# 1-Schematic_testflight2_pcb.net
KiCad netlist of a schematic drawn in EasyEDA
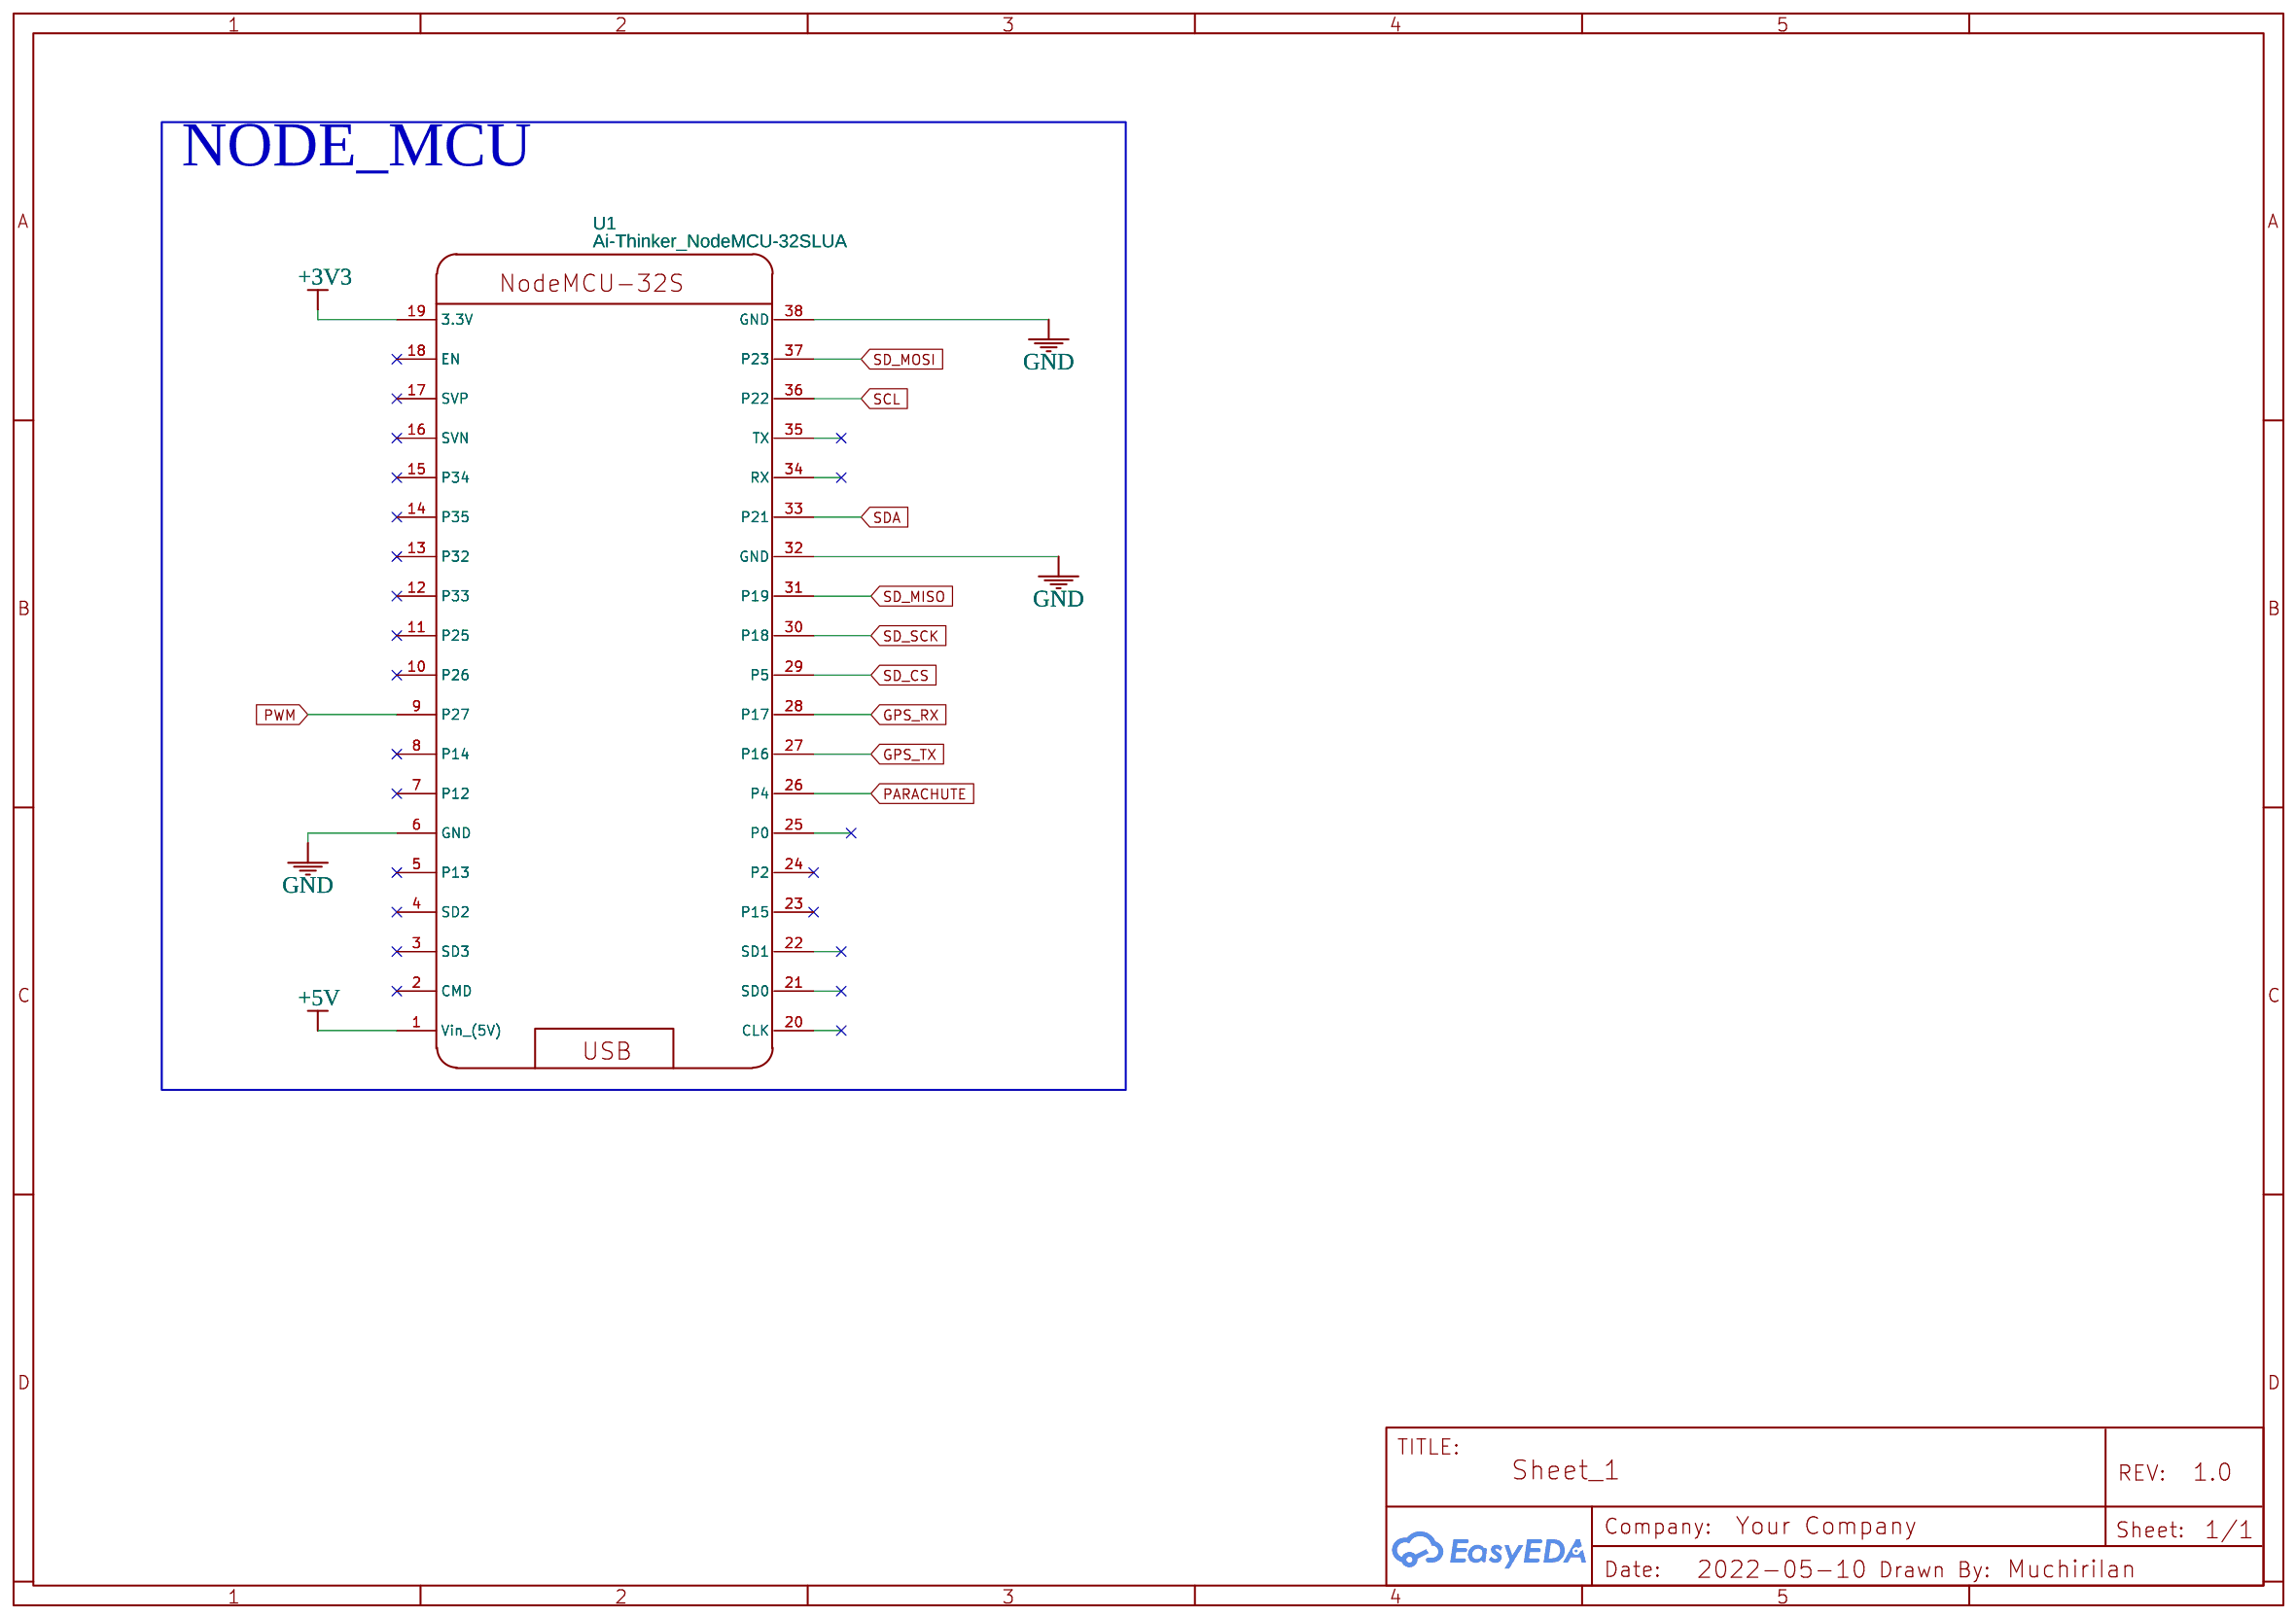
[diagram p0: Sheet_1]
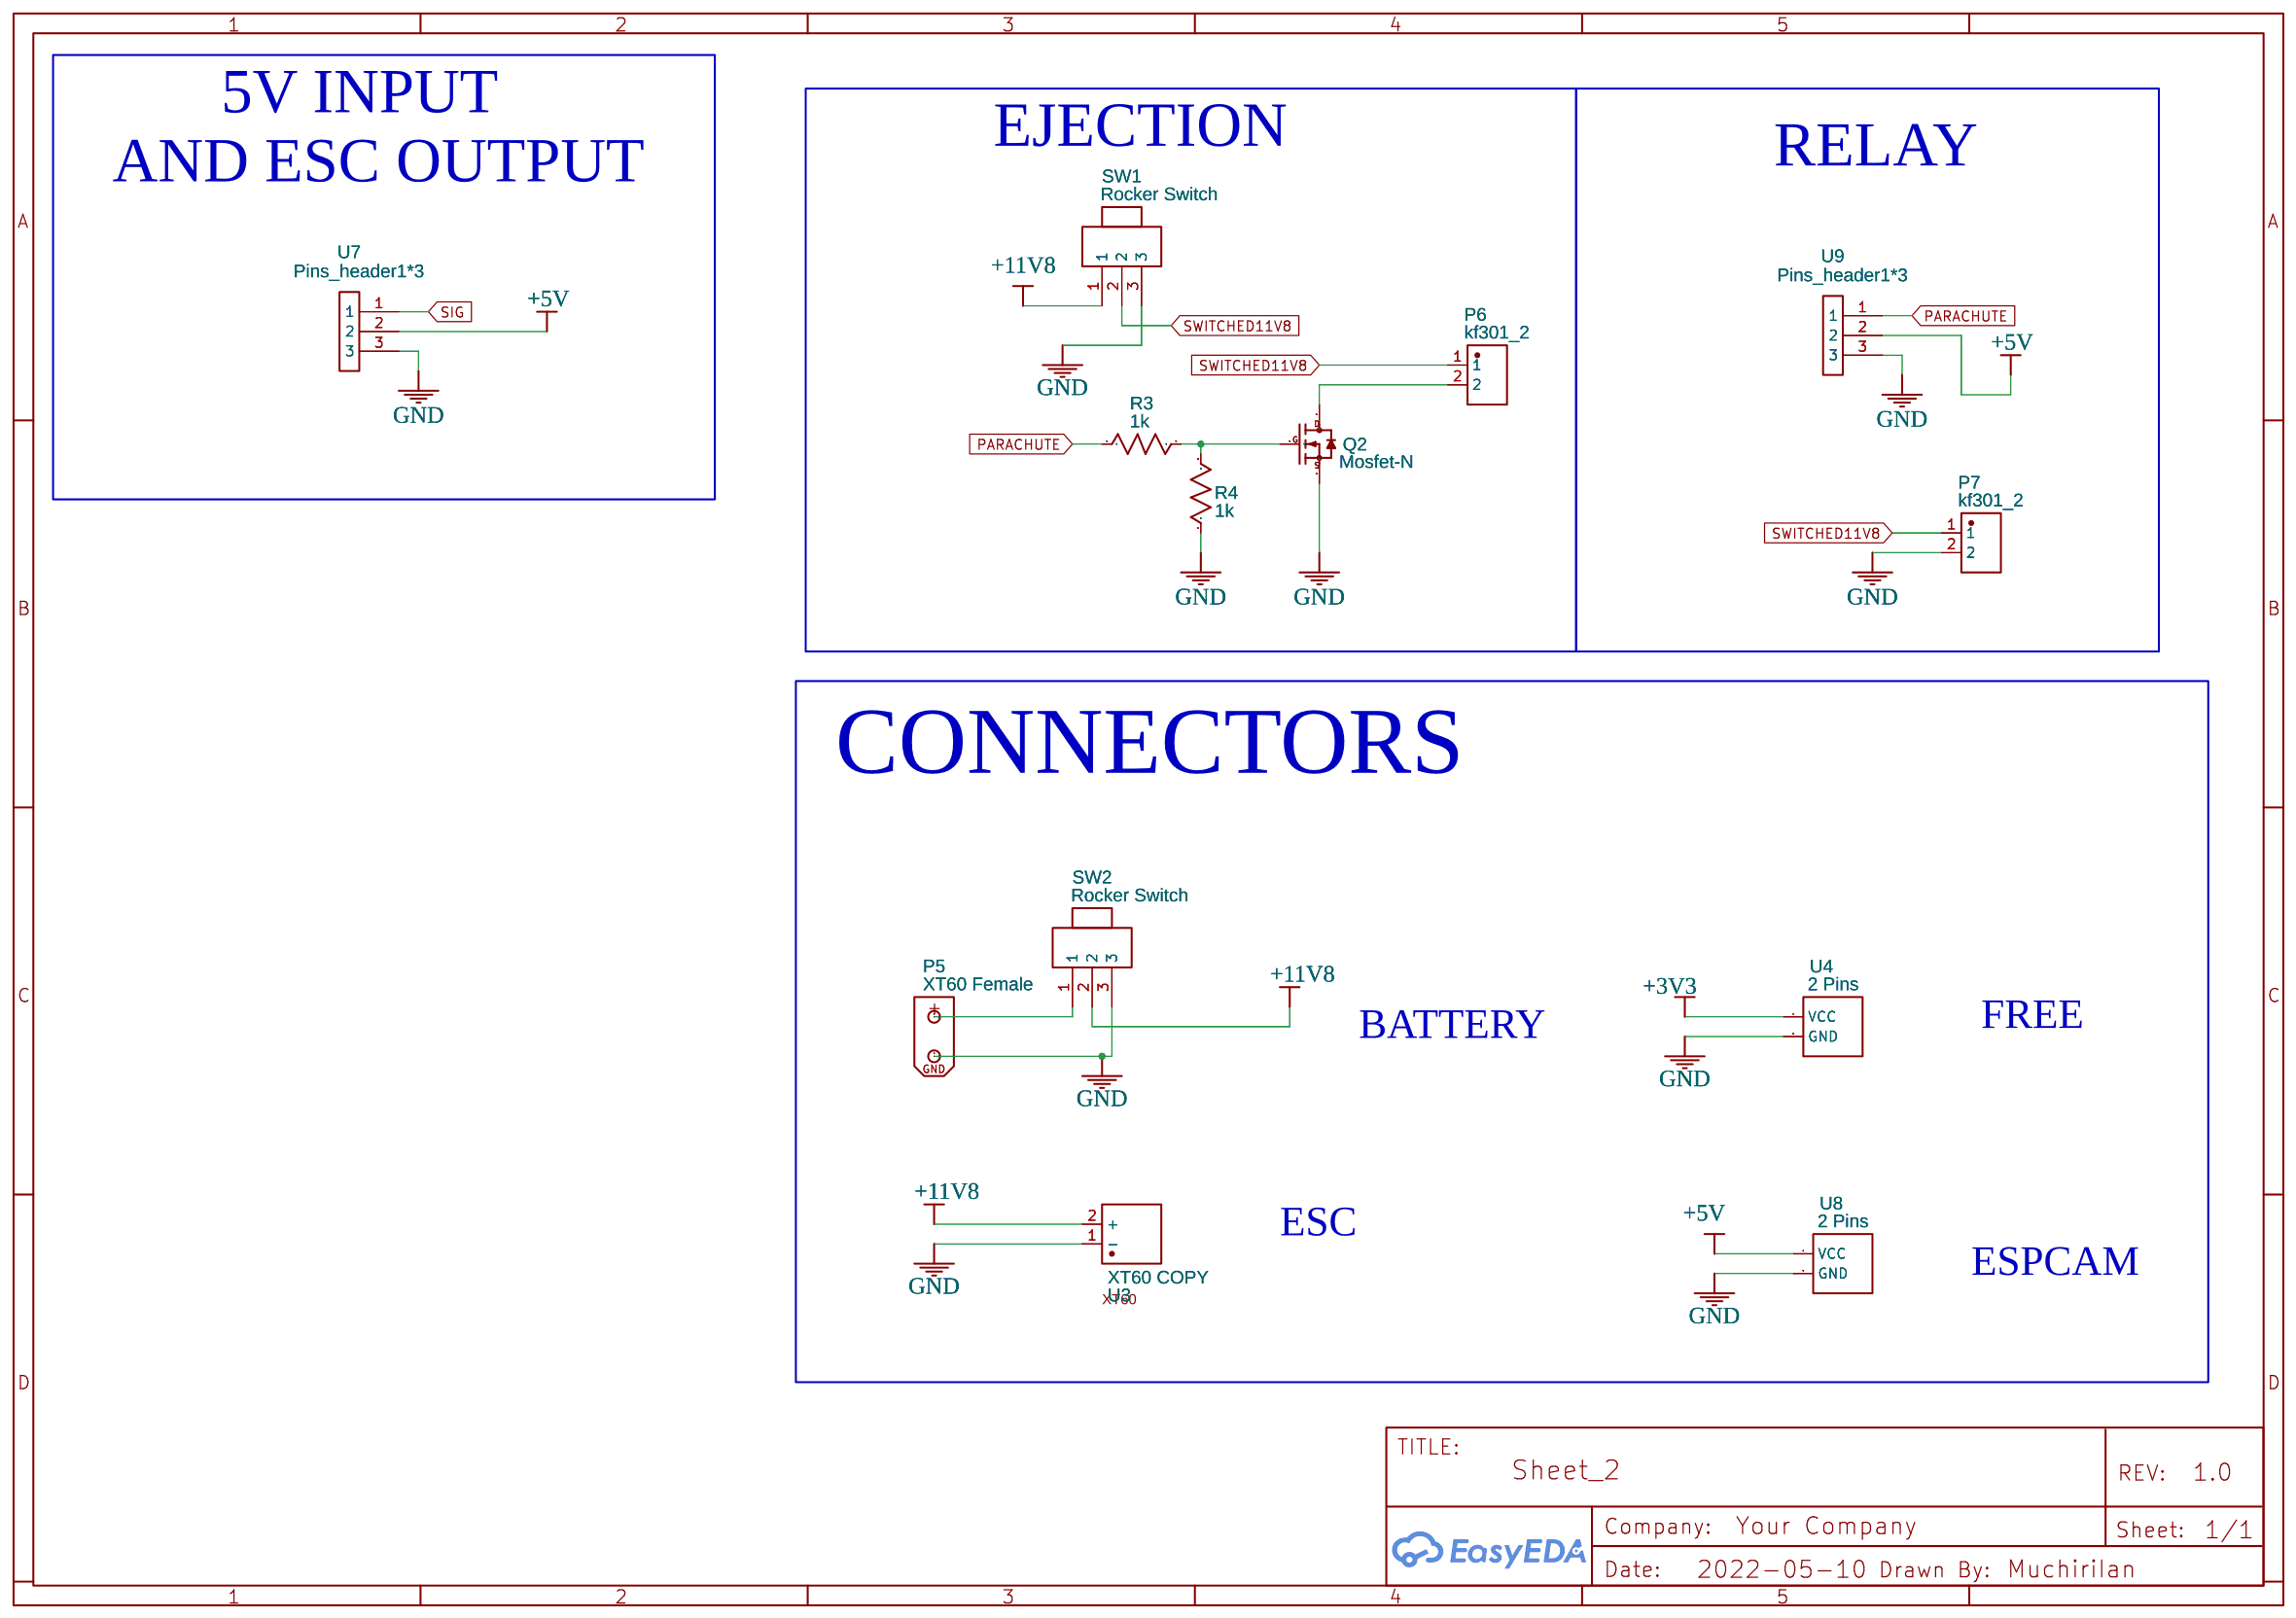
[diagram p1: Sheet_2]
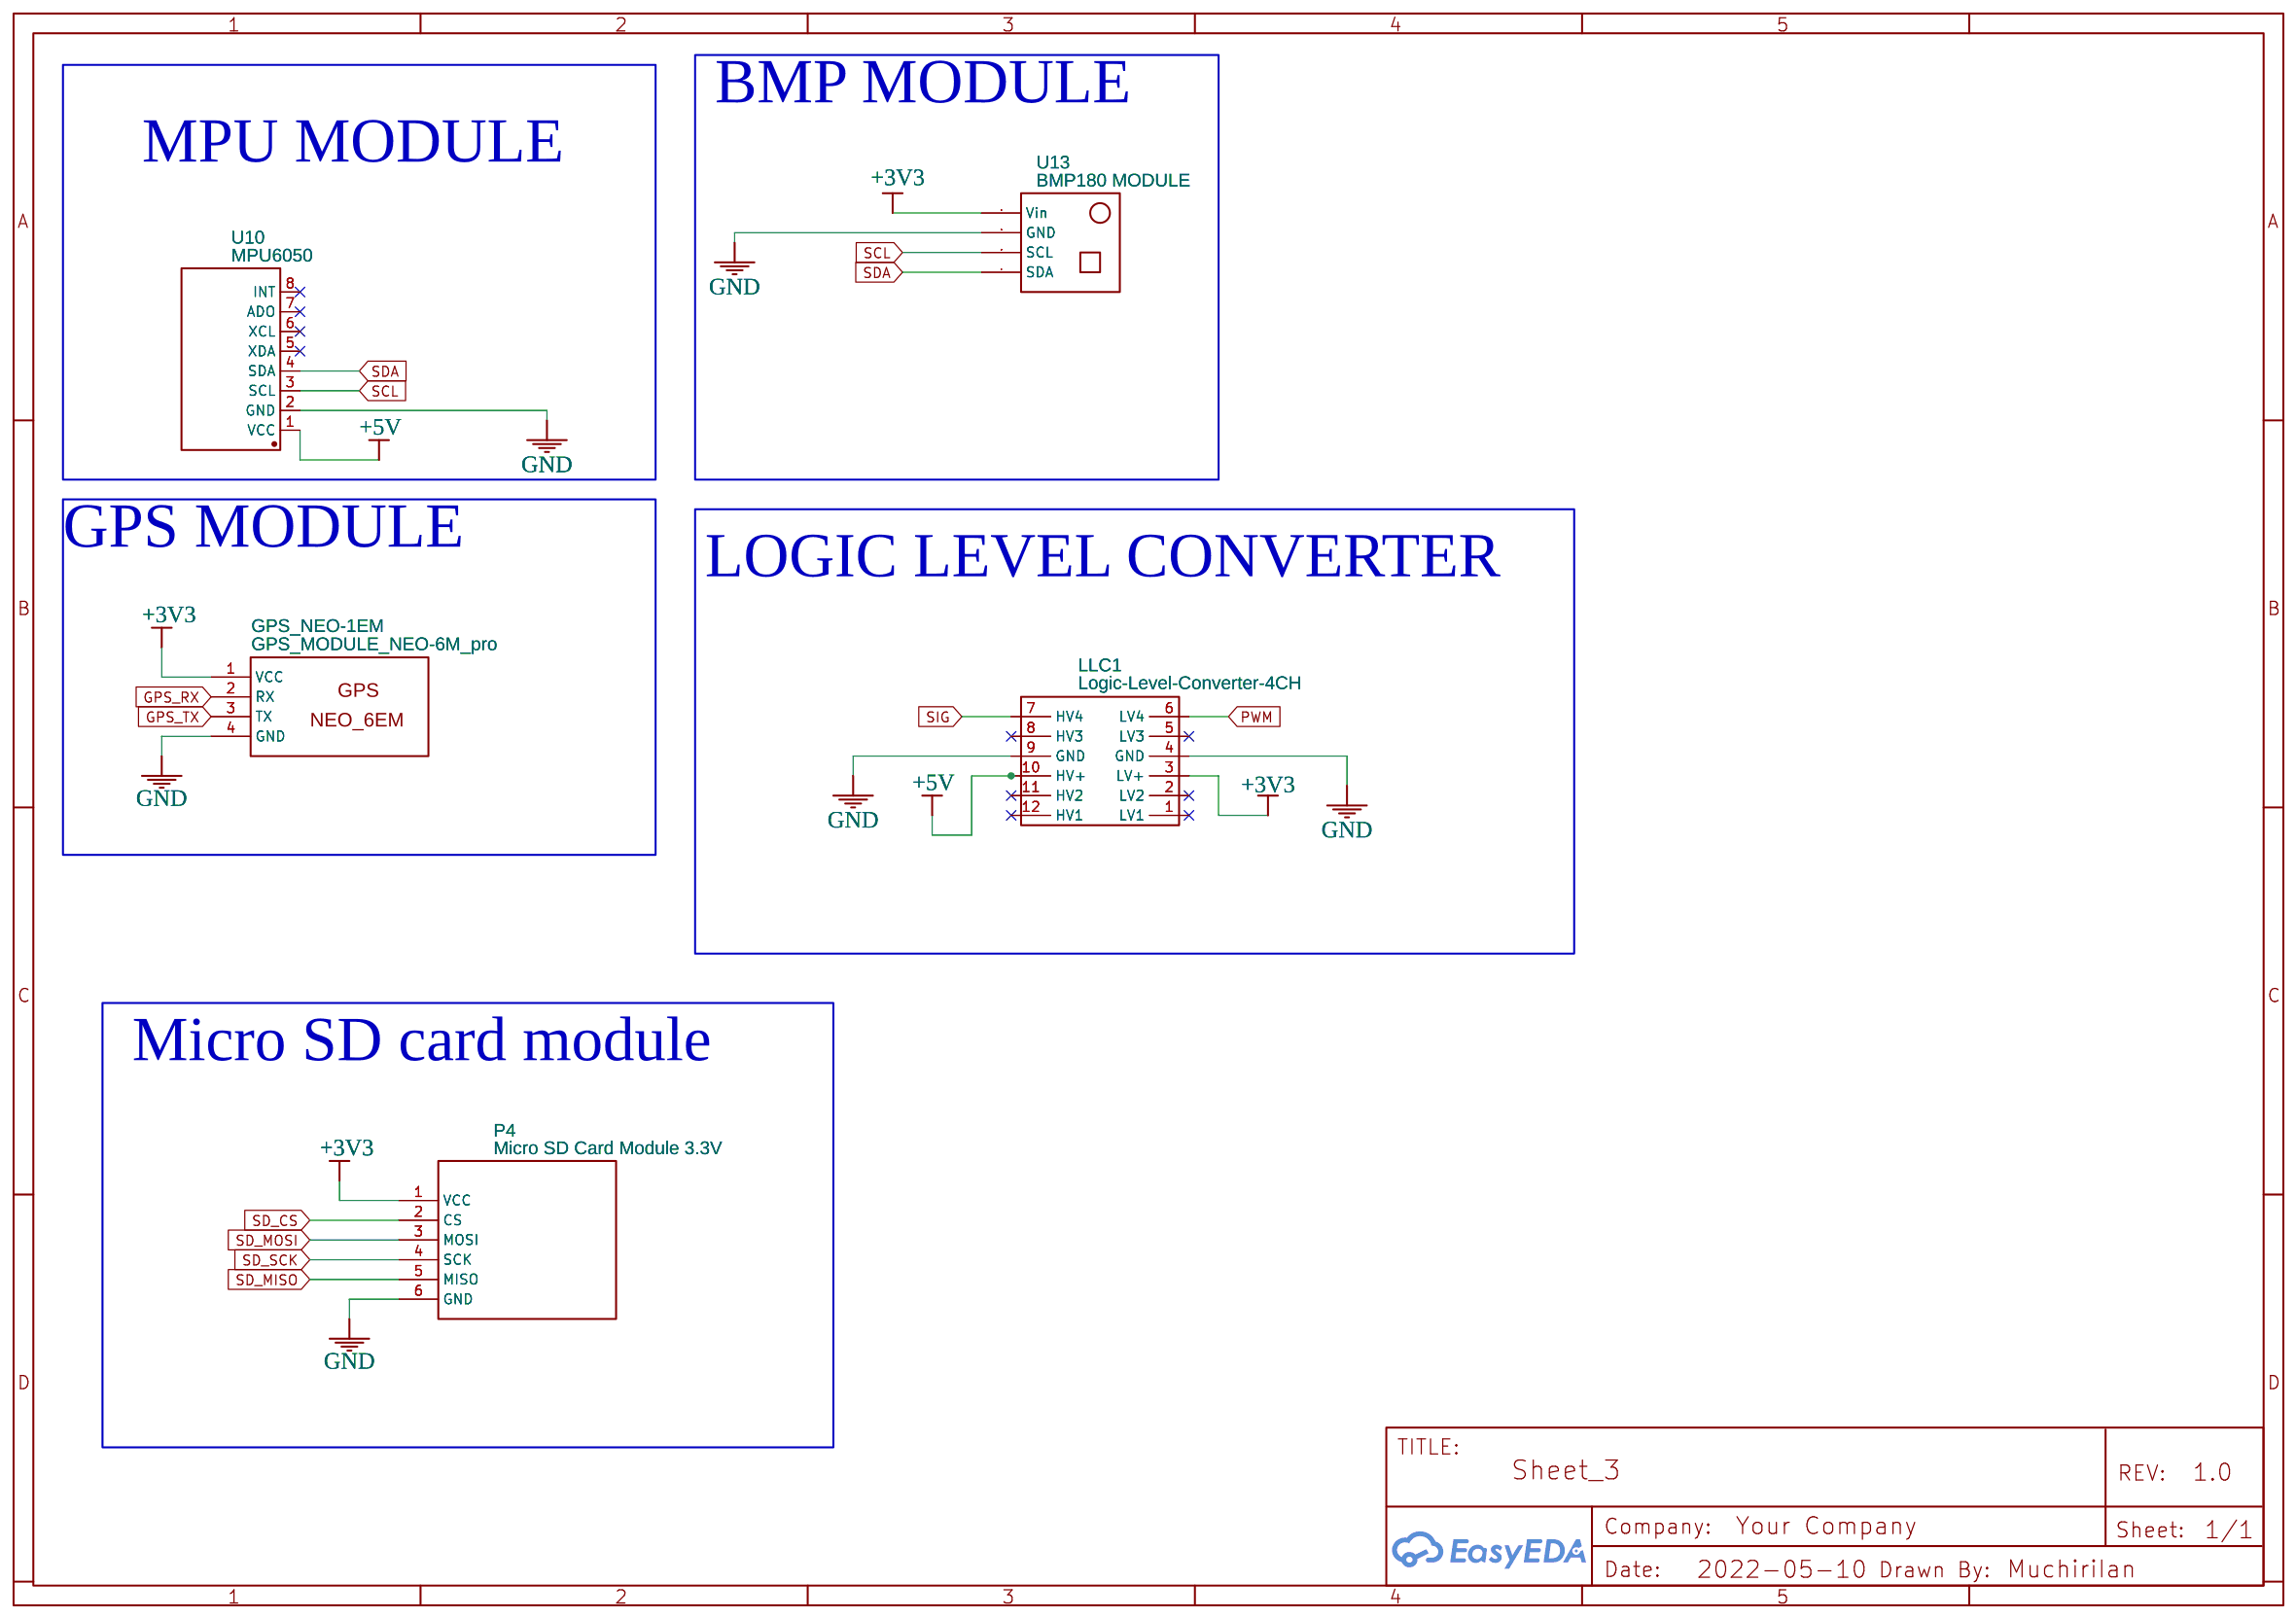
[diagram p2: Sheet_3]

(export (version "E")
  (design (tool "Eeschema 10.0.6"))
  (components
    (comp (ref "U1")
      (value "Ai-Thinker_NodeMCU-32SLUA")
      (fields
        (field (name "BOM_Manufacturer Part") "NodeMCU-32SLua")
        (field (name "BOM_Supplier Part") "C111436")
      )
      (libsource (lib "") (part "Ai-Thinker_NodeMCU-32SLUA"))
    )
    (comp (ref "P5")
      (value "XT60 Female")
      (fields (field (name "BOM_Manufacturer Part") "XT60-F"))
      (libsource (lib "") (part "XT60 Female"))
    )
    (comp (ref "P6")
      (value "kf301_2")
      (fields (field (name "BOM_Supplier Part") "C33435"))
      (libsource (lib "") (part "kf301_2"))
    )
    (comp (ref "P7")
      (value "kf301_2")
      (fields (field (name "BOM_Supplier Part") "C33435"))
      (libsource (lib "") (part "kf301_2"))
    )
    (comp (ref "Q2") (value "Mosfet-N") (libsource (lib "") (part "Mosfet-N")))
    (comp (ref "R3") (value "1k") (libsource (lib "") (part "R_AXIAL-0.6_US")))
    (comp (ref "R4") (value "1k") (libsource (lib "") (part "R_AXIAL-0.6_US_1")))
    (comp (ref "SW1") (value "Rocker Switch") (libsource (lib "") (part "Rocker Switch")))
    (comp (ref "SW2") (value "Rocker Switch") (libsource (lib "") (part "Rocker Switch")))
    (comp (ref "U3") (value "XT60 COPY") (libsource (lib "") (part "XT60 COPY")))
    (comp (ref "U4") (value "2 Pins") (libsource (lib "") (part "2 Pins")))
    (comp (ref "U7") (value "Pins_header1*3") (libsource (lib "") (part "Pins_header1*3")))
    (comp (ref "U8") (value "2 Pins") (libsource (lib "") (part "2 Pins")))
    (comp (ref "U9") (value "Pins_header1*3") (libsource (lib "") (part "Pins_header1*3")))
    (comp (ref "GPS_NEO-1EM")
      (value "GPS_MODULE_NEO-6M_pro")
      (libsource (lib "") (part "GPS_MODULE_NEO-6M_pro"))
    )
    (comp (ref "LLC1")
      (value "Logic-Level-Converter-4CH")
      (fields (field (name "BOM_Supplier Part") "50807"))
      (libsource (lib "") (part "Logic-Level-Converter-4CH"))
    )
    (comp (ref "P4")
      (value "Micro SD Card Module 3.3V")
      (libsource (lib "") (part "Micro SD Card Module 3.3V"))
    )
    (comp (ref "U10")
      (value "MPU6050")
      (fields (field (name "BOM_Supplier Part") "GY521"))
      (libsource (lib "") (part "MPU6050"))
    )
    (comp (ref "U13")
      (value "BMP180 MODULE")
      (fields (field (name "BOM_Manufacturer Part") "BMP180 (HW-596)"))
      (libsource (lib "") (part "BMP180 MODULE"))
    )
  )
  (nets
    (net (code "1") (name "+3V3") (class "Default")
      (node (ref "GPS_NEO-1EM") (pin "1") (pinfunction "VCC_1") (pintype "passive"))
      (node (ref "LLC1") (pin "3") (pinfunction "LV+_3") (pintype "unspecified"))
      (node (ref "P4") (pin "1") (pinfunction "VCC_1") (pintype "unspecified"))
      (node (ref "U1") (pin "19") (pinfunction "3.3V_19") (pintype "unspecified"))
      (node (ref "U13") (pin "1") (pinfunction "Vin_1") (pintype "unspecified"))
      (node (ref "U4") (pin "1") (pinfunction "VCC_1") (pintype "unspecified"))
    )
    (net (code "2") (name "+5V") (class "Default")
      (node (ref "LLC1") (pin "10") (pinfunction "HV+_10") (pintype "unspecified"))
      (node (ref "U1") (pin "1") (pinfunction "Vin_(5V)_1") (pintype "unspecified"))
      (node (ref "U10") (pin "1") (pinfunction "VCC_1") (pintype "unspecified"))
      (node (ref "U7") (pin "2") (pinfunction "2_2") (pintype "unspecified"))
      (node (ref "U8") (pin "1") (pinfunction "VCC_1") (pintype "unspecified"))
      (node (ref "U9") (pin "2") (pinfunction "2_2") (pintype "unspecified"))
    )
    (net (code "3") (name "+11V8") (class "Default")
      (node (ref "SW1") (pin "1") (pinfunction "1_1") (pintype "unspecified"))
      (node (ref "SW2") (pin "2") (pinfunction "2_2") (pintype "unspecified"))
      (node (ref "U3") (pin "2") (pinfunction "+_2") (pintype "unspecified"))
    )
    (net (code "4") (name "GND") (class "Default")
      (node (ref "GPS_NEO-1EM") (pin "4") (pinfunction "GND_4") (pintype "passive"))
      (node (ref "LLC1") (pin "4") (pinfunction "GND_4") (pintype "unspecified"))
      (node (ref "LLC1") (pin "9") (pinfunction "GND_9") (pintype "unspecified"))
      (node (ref "P4") (pin "6") (pinfunction "GND_6") (pintype "unspecified"))
      (node (ref "P5") (pin "1") (pinfunction "1_1") (pintype "unspecified"))
      (node (ref "P7") (pin "2") (pinfunction "2_2") (pintype "unspecified"))
      (node (ref "Q2") (pin "3") (pinfunction "S_3") (pintype "unspecified"))
      (node (ref "R4") (pin "1") (pinfunction "1_1") (pintype "unspecified"))
      (node (ref "SW1") (pin "3") (pinfunction "3_3") (pintype "unspecified"))
      (node (ref "SW2") (pin "3") (pinfunction "3_3") (pintype "unspecified"))
      (node (ref "U1") (pin "32") (pinfunction "GND_32") (pintype "unspecified"))
      (node (ref "U1") (pin "38") (pinfunction "GND_38") (pintype "unspecified"))
      (node (ref "U1") (pin "6") (pinfunction "GND_6") (pintype "unspecified"))
      (node (ref "U10") (pin "2") (pinfunction "GND_2") (pintype "unspecified"))
      (node (ref "U13") (pin "2") (pinfunction "GND_2") (pintype "unspecified"))
      (node (ref "U3") (pin "1") (pinfunction "-_1") (pintype "unspecified"))
      (node (ref "U4") (pin "2") (pinfunction "GND_2") (pintype "unspecified"))
      (node (ref "U7") (pin "3") (pinfunction "3_3") (pintype "unspecified"))
      (node (ref "U8") (pin "2") (pinfunction "GND_2") (pintype "unspecified"))
      (node (ref "U9") (pin "3") (pinfunction "3_3") (pintype "unspecified"))
    )
    (net (code "5") (name "GPS_RX") (class "Default")
      (node (ref "GPS_NEO-1EM") (pin "2") (pinfunction "RX_2") (pintype "input"))
      (node (ref "U1") (pin "28") (pinfunction "P17_28") (pintype "unspecified"))
    )
    (net (code "6") (name "GPS_TX") (class "Default")
      (node (ref "GPS_NEO-1EM") (pin "3") (pinfunction "TX_3") (pintype "output"))
      (node (ref "U1") (pin "27") (pinfunction "P16_27") (pintype "unspecified"))
    )
    (net (code "7") (name "Net-(P5-Pad2)") (class "Default")
      (node (ref "P5") (pin "2") (pinfunction "2_2") (pintype "unspecified"))
      (node (ref "SW2") (pin "1") (pinfunction "1_1") (pintype "unspecified"))
    )
    (net (code "8") (name "Net-(Q2-D)") (class "Default")
      (node (ref "P6") (pin "2") (pinfunction "2_2") (pintype "unspecified"))
      (node (ref "Q2") (pin "2") (pinfunction "D_2") (pintype "unspecified"))
    )
    (net (code "9") (name "Net-(Q2-G)") (class "Default")
      (node (ref "Q2") (pin "1") (pinfunction "G_1") (pintype "unspecified"))
      (node (ref "R3") (pin "2") (pinfunction "2_2") (pintype "unspecified"))
      (node (ref "R4") (pin "2") (pinfunction "2_2") (pintype "unspecified"))
    )
    (net (code "10") (name "PARACHUTE") (class "Default")
      (node (ref "R3") (pin "1") (pinfunction "1_1") (pintype "unspecified"))
      (node (ref "U1") (pin "26") (pinfunction "P4_26") (pintype "unspecified"))
      (node (ref "U9") (pin "1") (pinfunction "1_1") (pintype "unspecified"))
    )
    (net (code "11") (name "PWM") (class "Default")
      (node (ref "LLC1") (pin "6") (pinfunction "LV4_6") (pintype "unspecified"))
      (node (ref "U1") (pin "9") (pinfunction "P27_9") (pintype "unspecified"))
    )
    (net (code "12") (name "SCL") (class "Default")
      (node (ref "U1") (pin "36") (pinfunction "P22_36") (pintype "unspecified"))
      (node (ref "U10") (pin "3") (pinfunction "SCL_3") (pintype "unspecified"))
      (node (ref "U13") (pin "3") (pinfunction "SCL_3") (pintype "unspecified"))
    )
    (net (code "13") (name "SDA") (class "Default")
      (node (ref "U1") (pin "33") (pinfunction "P21_33") (pintype "unspecified"))
      (node (ref "U10") (pin "4") (pinfunction "SDA_4") (pintype "unspecified"))
      (node (ref "U13") (pin "4") (pinfunction "SDA_4") (pintype "unspecified"))
    )
    (net (code "14") (name "SD_CS") (class "Default")
      (node (ref "P4") (pin "2") (pinfunction "CS_2") (pintype "unspecified"))
      (node (ref "U1") (pin "29") (pinfunction "P5_29") (pintype "unspecified"))
    )
    (net (code "15") (name "SD_MISO") (class "Default")
      (node (ref "P4") (pin "5") (pinfunction "MISO_5") (pintype "unspecified"))
      (node (ref "U1") (pin "31") (pinfunction "P19_31") (pintype "unspecified"))
    )
    (net (code "16") (name "SD_MOSI") (class "Default")
      (node (ref "P4") (pin "3") (pinfunction "MOSI_3") (pintype "unspecified"))
      (node (ref "U1") (pin "37") (pinfunction "P23_37") (pintype "unspecified"))
    )
    (net (code "17") (name "SD_SCK") (class "Default")
      (node (ref "P4") (pin "4") (pinfunction "SCK_4") (pintype "unspecified"))
      (node (ref "U1") (pin "30") (pinfunction "P18_30") (pintype "unspecified"))
    )
    (net (code "18") (name "SIG") (class "Default")
      (node (ref "LLC1") (pin "7") (pinfunction "HV4_7") (pintype "unspecified"))
      (node (ref "U7") (pin "1") (pinfunction "1_1") (pintype "unspecified"))
    )
    (net (code "19") (name "SWITCHED11V8") (class "Default")
      (node (ref "P6") (pin "1") (pinfunction "1_1") (pintype "unspecified"))
      (node (ref "P7") (pin "1") (pinfunction "1_1") (pintype "unspecified"))
      (node (ref "SW1") (pin "2") (pinfunction "2_2") (pintype "unspecified"))
    )
    (net (code "20") (name "unconnected-(LLC1-HV1-Pad12)") (class "Default")
      (node (ref "LLC1") (pin "12") (pinfunction "HV1_12") (pintype "unspecified+no_connect"))
    )
    (net (code "21") (name "unconnected-(LLC1-HV2-Pad11)") (class "Default")
      (node (ref "LLC1") (pin "11") (pinfunction "HV2_11") (pintype "unspecified+no_connect"))
    )
    (net (code "22") (name "unconnected-(LLC1-HV3-Pad8)") (class "Default")
      (node (ref "LLC1") (pin "8") (pinfunction "HV3_8") (pintype "unspecified+no_connect"))
    )
    (net (code "23") (name "unconnected-(LLC1-LV1-Pad1)") (class "Default")
      (node (ref "LLC1") (pin "1") (pinfunction "LV1_1") (pintype "unspecified+no_connect"))
    )
    (net (code "24") (name "unconnected-(LLC1-LV2-Pad2)") (class "Default")
      (node (ref "LLC1") (pin "2") (pinfunction "LV2_2") (pintype "unspecified+no_connect"))
    )
    (net (code "25") (name "unconnected-(LLC1-LV3-Pad5)") (class "Default")
      (node (ref "LLC1") (pin "5") (pinfunction "LV3_5") (pintype "unspecified+no_connect"))
    )
    (net (code "26") (name "unconnected-(U1-CLK-Pad20)") (class "Default")
      (node (ref "U1") (pin "20") (pinfunction "CLK_20") (pintype "unspecified+no_connect"))
    )
    (net (code "27") (name "unconnected-(U1-CMD-Pad2)") (class "Default")
      (node (ref "U1") (pin "2") (pinfunction "CMD_2") (pintype "unspecified+no_connect"))
    )
    (net (code "28") (name "unconnected-(U1-EN-Pad18)") (class "Default")
      (node (ref "U1") (pin "18") (pinfunction "EN_18") (pintype "unspecified+no_connect"))
    )
    (net (code "29") (name "unconnected-(U1-P0-Pad25)") (class "Default")
      (node (ref "U1") (pin "25") (pinfunction "P0_25") (pintype "unspecified+no_connect"))
    )
    (net (code "30") (name "unconnected-(U1-P2-Pad24)") (class "Default")
      (node (ref "U1") (pin "24") (pinfunction "P2_24") (pintype "unspecified+no_connect"))
    )
    (net (code "31") (name "unconnected-(U1-P12-Pad7)") (class "Default")
      (node (ref "U1") (pin "7") (pinfunction "P12_7") (pintype "unspecified+no_connect"))
    )
    (net (code "32") (name "unconnected-(U1-P13-Pad5)") (class "Default")
      (node (ref "U1") (pin "5") (pinfunction "P13_5") (pintype "unspecified+no_connect"))
    )
    (net (code "33") (name "unconnected-(U1-P14-Pad8)") (class "Default")
      (node (ref "U1") (pin "8") (pinfunction "P14_8") (pintype "unspecified+no_connect"))
    )
    (net (code "34") (name "unconnected-(U1-P15-Pad23)") (class "Default")
      (node (ref "U1") (pin "23") (pinfunction "P15_23") (pintype "unspecified+no_connect"))
    )
    (net (code "35") (name "unconnected-(U1-P25-Pad11)") (class "Default")
      (node (ref "U1") (pin "11") (pinfunction "P25_11") (pintype "unspecified+no_connect"))
    )
    (net (code "36") (name "unconnected-(U1-P26-Pad10)") (class "Default")
      (node (ref "U1") (pin "10") (pinfunction "P26_10") (pintype "unspecified+no_connect"))
    )
    (net (code "37") (name "unconnected-(U1-P32-Pad13)") (class "Default")
      (node (ref "U1") (pin "13") (pinfunction "P32_13") (pintype "unspecified+no_connect"))
    )
    (net (code "38") (name "unconnected-(U1-P33-Pad12)") (class "Default")
      (node (ref "U1") (pin "12") (pinfunction "P33_12") (pintype "unspecified+no_connect"))
    )
    (net (code "39") (name "unconnected-(U1-P34-Pad15)") (class "Default")
      (node (ref "U1") (pin "15") (pinfunction "P34_15") (pintype "unspecified+no_connect"))
    )
    (net (code "40") (name "unconnected-(U1-P35-Pad14)") (class "Default")
      (node (ref "U1") (pin "14") (pinfunction "P35_14") (pintype "unspecified+no_connect"))
    )
    (net (code "41") (name "unconnected-(U1-RX-Pad34)") (class "Default")
      (node (ref "U1") (pin "34") (pinfunction "RX_34") (pintype "unspecified+no_connect"))
    )
    (net (code "42") (name "unconnected-(U1-SD0-Pad21)") (class "Default")
      (node (ref "U1") (pin "21") (pinfunction "SD0_21") (pintype "unspecified+no_connect"))
    )
    (net (code "43") (name "unconnected-(U1-SD1-Pad22)") (class "Default")
      (node (ref "U1") (pin "22") (pinfunction "SD1_22") (pintype "unspecified+no_connect"))
    )
    (net (code "44") (name "unconnected-(U1-SD2-Pad4)") (class "Default")
      (node (ref "U1") (pin "4") (pinfunction "SD2_4") (pintype "unspecified+no_connect"))
    )
    (net (code "45") (name "unconnected-(U1-SD3-Pad3)") (class "Default")
      (node (ref "U1") (pin "3") (pinfunction "SD3_3") (pintype "unspecified+no_connect"))
    )
    (net (code "46") (name "unconnected-(U1-SVN-Pad16)") (class "Default")
      (node (ref "U1") (pin "16") (pinfunction "SVN_16") (pintype "unspecified+no_connect"))
    )
    (net (code "47") (name "unconnected-(U1-SVP-Pad17)") (class "Default")
      (node (ref "U1") (pin "17") (pinfunction "SVP_17") (pintype "unspecified+no_connect"))
    )
    (net (code "48") (name "unconnected-(U1-TX-Pad35)") (class "Default")
      (node (ref "U1") (pin "35") (pinfunction "TX_35") (pintype "unspecified+no_connect"))
    )
    (net (code "49") (name "unconnected-(U10-ADO-Pad7)") (class "Default")
      (node (ref "U10") (pin "7") (pinfunction "ADO_7") (pintype "unspecified+no_connect"))
    )
    (net (code "50") (name "unconnected-(U10-INT-Pad8)") (class "Default")
      (node (ref "U10") (pin "8") (pinfunction "INT_8") (pintype "unspecified+no_connect"))
    )
    (net (code "51") (name "unconnected-(U10-XCL-Pad6)") (class "Default")
      (node (ref "U10") (pin "6") (pinfunction "XCL_6") (pintype "unspecified+no_connect"))
    )
    (net (code "52") (name "unconnected-(U10-XDA-Pad5)") (class "Default")
      (node (ref "U10") (pin "5") (pinfunction "XDA_5") (pintype "unspecified+no_connect"))
    )
  )
)
